# Schemat.net
KiCad netlist of a schematic drawn in Altium Designer
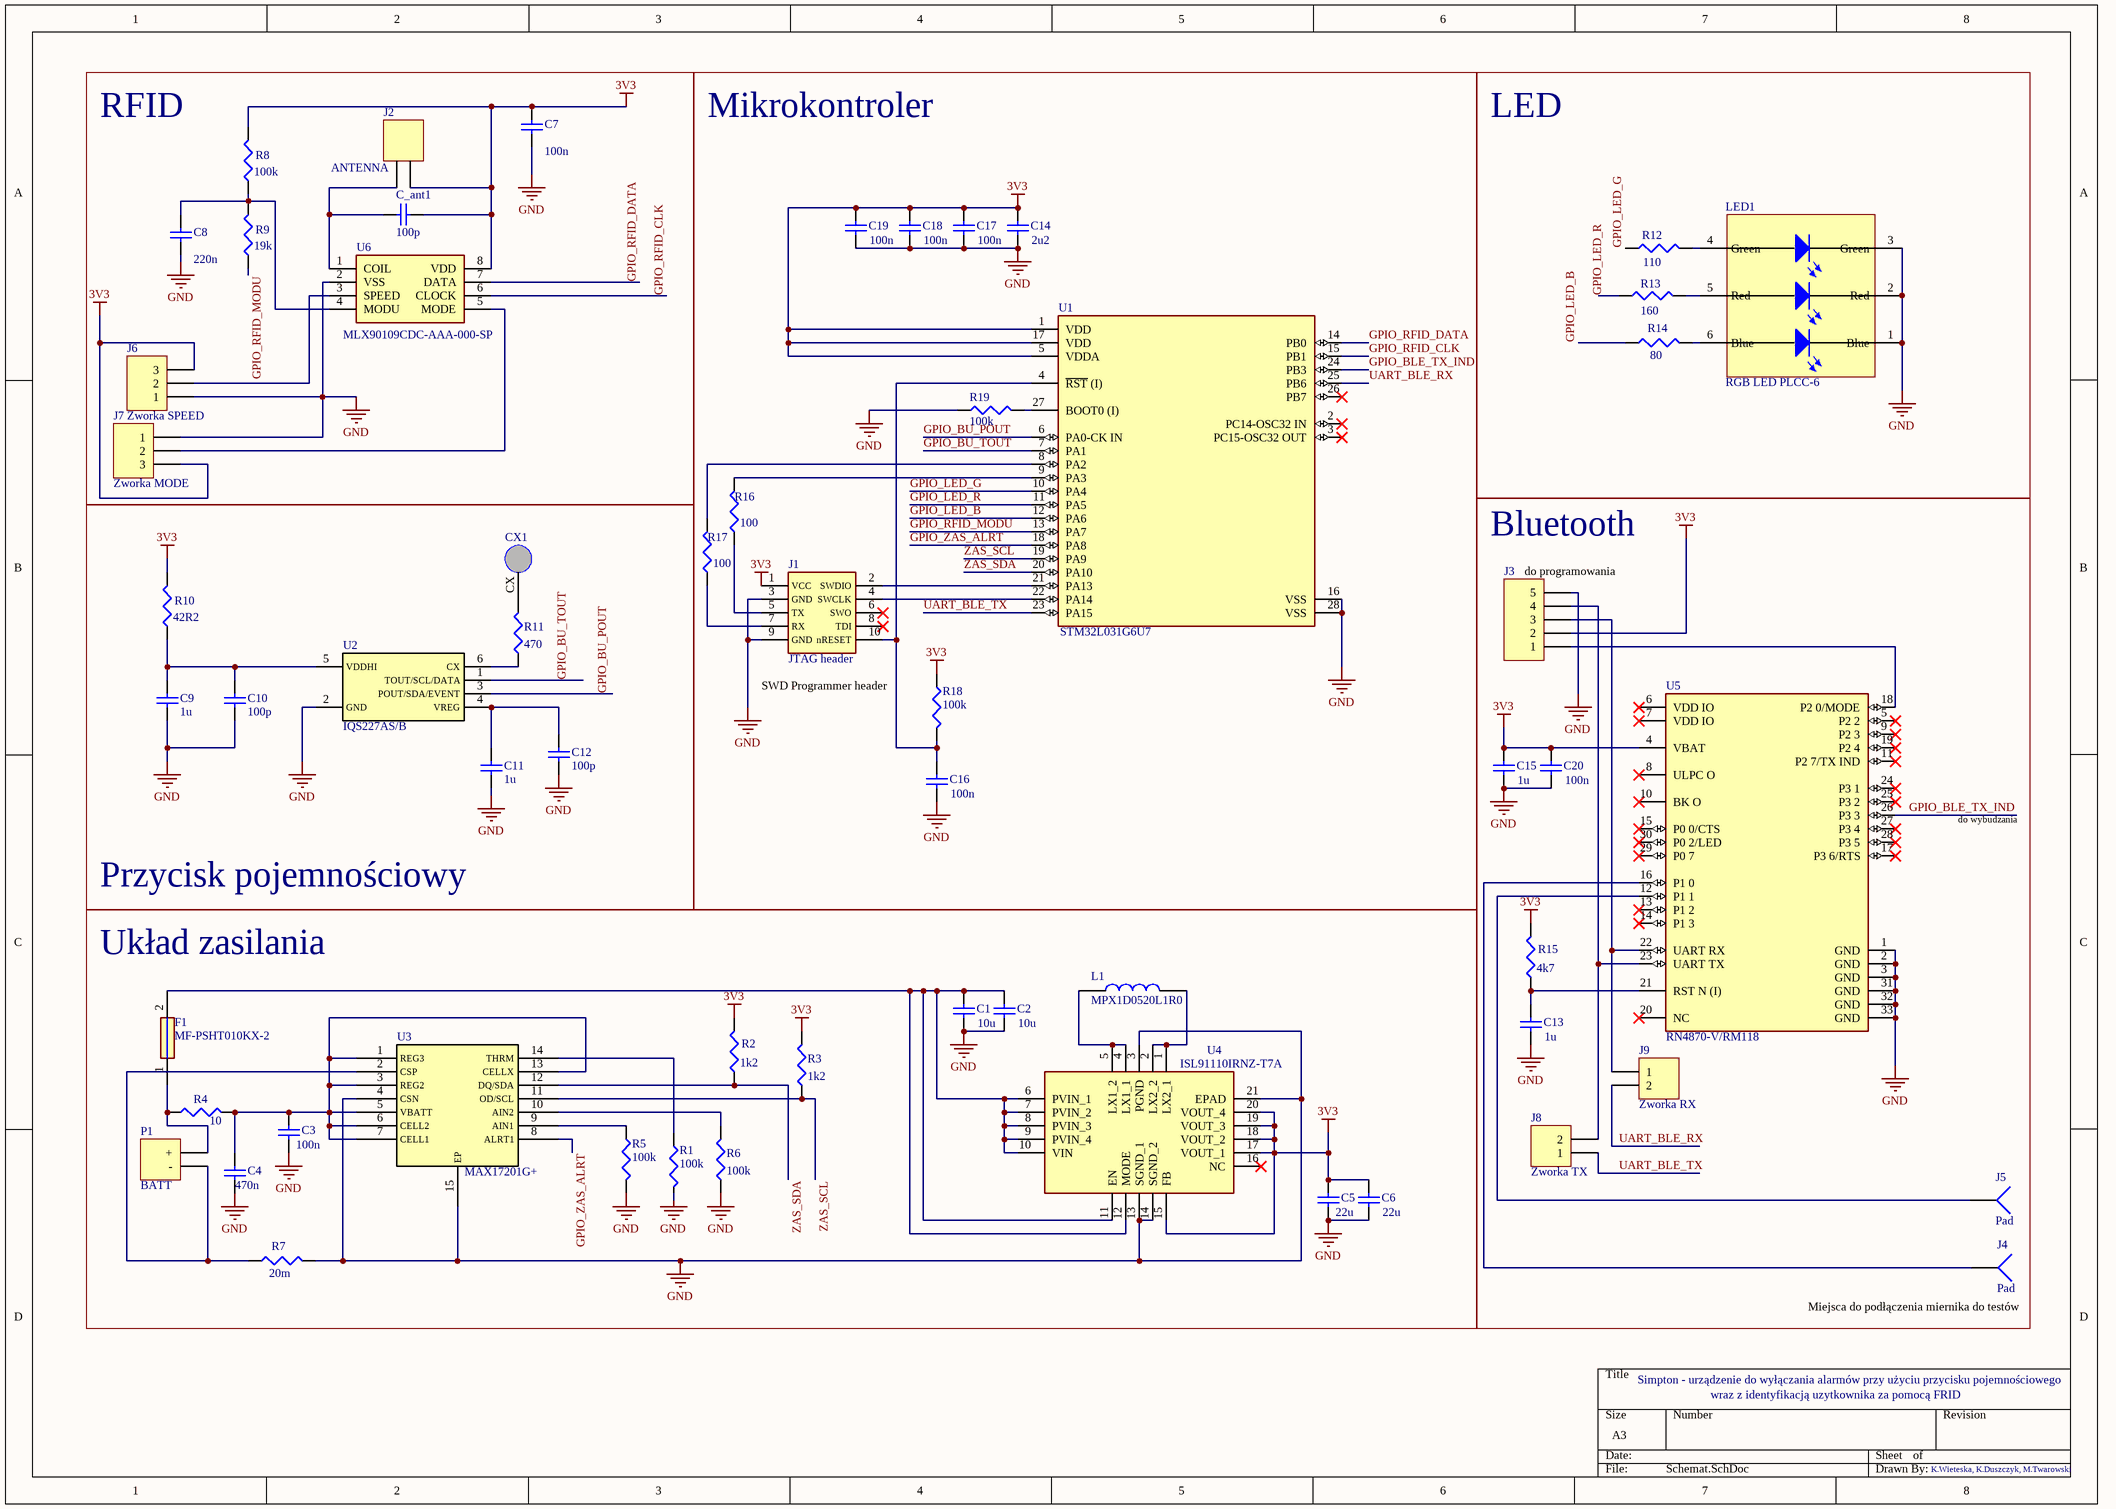
[diagram p0: Schemat.SchDoc]

(export (version "E")
  (design (tool "Eeschema 10.0.6"))
  (components
    (comp (ref "C1")
      (value "10u")
      (footprint "1608[0603]")
      (description "Capacitor (Semiconductor SIM Model)")
      (fields (field (name "Comment") "Cap Semi") (field (name "PUBLISHER") "Altium Limited"))
      (libsource (lib "Miscellaneous Devices") (part "Cap Semi"))
    )
    (comp (ref "C2")
      (value "10u")
      (footprint "1608[0603]")
      (description "Capacitor (Semiconductor SIM Model)")
      (fields (field (name "Comment") "Cap Semi") (field (name "PUBLISHER") "Altium Limited"))
      (libsource (lib "Miscellaneous Devices") (part "Cap Semi"))
    )
    (comp (ref "C3")
      (value "100n")
      (footprint "0402")
      (description "Capacitor (Semiconductor SIM Model)")
      (fields (field (name "Comment") "Cap Semi") (field (name "PUBLISHER") "Altium Limited"))
      (libsource (lib "Miscellaneous Devices") (part "Cap Semi"))
    )
    (comp (ref "C4")
      (value "470n")
      (footprint "0402")
      (description "Capacitor (Semiconductor SIM Model)")
      (fields (field (name "Comment") "Cap Semi") (field (name "PUBLISHER") "Altium Limited"))
      (libsource (lib "Miscellaneous Devices") (part "Cap Semi"))
    )
    (comp (ref "C5")
      (value "22u")
      (footprint "1608[0603]")
      (description "Capacitor (Semiconductor SIM Model)")
      (fields (field (name "Comment") "Cap Semi") (field (name "PUBLISHER") "Altium Limited"))
      (libsource (lib "Miscellaneous Devices") (part "Cap Semi"))
    )
    (comp (ref "C6")
      (value "22u")
      (footprint "1608[0603]")
      (description "Capacitor (Semiconductor SIM Model)")
      (fields (field (name "Comment") "Cap Semi") (field (name "PUBLISHER") "Altium Limited"))
      (libsource (lib "Miscellaneous Devices") (part "Cap Semi"))
    )
    (comp (ref "C7")
      (value "100n")
      (footprint "0402")
      (description "Capacitor (Semiconductor SIM Model)")
      (fields (field (name "Comment") "Cap Semi") (field (name "PUBLISHER") "Altium Limited"))
      (libsource (lib "Miscellaneous Devices") (part "Cap Semi"))
    )
    (comp (ref "C8")
      (value "220n")
      (footprint "0402")
      (description "Capacitor (Semiconductor SIM Model)")
      (fields (field (name "Comment") "Cap Semi") (field (name "PUBLISHER") "Altium Limited"))
      (libsource (lib "Miscellaneous Devices") (part "Cap Semi"))
    )
    (comp (ref "C9")
      (value "1u")
      (footprint "0402")
      (description "Capacitor (Semiconductor SIM Model)")
      (fields (field (name "Comment") "Cap Semi") (field (name "PUBLISHER") "Altium Limited"))
      (libsource (lib "Miscellaneous Devices") (part "Cap Semi"))
    )
    (comp (ref "C10")
      (value "100p")
      (footprint "0402")
      (description "Capacitor (Semiconductor SIM Model)")
      (fields (field (name "Comment") "Cap Semi") (field (name "PUBLISHER") "Altium Limited"))
      (libsource (lib "Miscellaneous Devices") (part "Cap Semi"))
    )
    (comp (ref "C11")
      (value "1u")
      (footprint "0402")
      (description "Capacitor (Semiconductor SIM Model)")
      (fields (field (name "Comment") "Cap Semi") (field (name "PUBLISHER") "Altium Limited"))
      (libsource (lib "Miscellaneous Devices") (part "Cap Semi"))
    )
    (comp (ref "C12")
      (value "100p")
      (footprint "0402")
      (description "Capacitor (Semiconductor SIM Model)")
      (fields (field (name "Comment") "Cap Semi") (field (name "PUBLISHER") "Altium Limited"))
      (libsource (lib "Miscellaneous Devices") (part "Cap Semi"))
    )
    (comp (ref "C13")
      (value "1u")
      (footprint "0402")
      (description "Capacitor (Semiconductor SIM Model)")
      (fields (field (name "Comment") "Cap Semi") (field (name "PUBLISHER") "Altium Limited"))
      (libsource (lib "Miscellaneous Devices") (part "Cap Semi"))
    )
    (comp (ref "C14")
      (value "2u2")
      (footprint "0402")
      (description "Capacitor (Semiconductor SIM Model)")
      (fields (field (name "Comment") "Cap Semi") (field (name "PUBLISHER") "Altium Limited"))
      (libsource (lib "Miscellaneous Devices") (part "Cap Semi"))
    )
    (comp (ref "C15")
      (value "1u")
      (footprint "0402")
      (description "Capacitor (Semiconductor SIM Model)")
      (fields (field (name "Comment") "Cap Semi") (field (name "PUBLISHER") "Altium Limited"))
      (libsource (lib "Miscellaneous Devices") (part "Cap Semi"))
    )
    (comp (ref "C16")
      (value "100n")
      (footprint "0402")
      (description "Capacitor (Semiconductor SIM Model)")
      (fields (field (name "Comment") "Cap Semi") (field (name "PUBLISHER") "Altium Limited"))
      (libsource (lib "Miscellaneous Devices") (part "Cap Semi"))
    )
    (comp (ref "C17")
      (value "100n")
      (footprint "0402")
      (description "Capacitor (Semiconductor SIM Model)")
      (fields (field (name "Comment") "Cap Semi") (field (name "PUBLISHER") "Altium Limited"))
      (libsource (lib "Miscellaneous Devices") (part "Cap Semi"))
    )
    (comp (ref "C18")
      (value "100n")
      (footprint "0402")
      (description "Capacitor (Semiconductor SIM Model)")
      (fields (field (name "Comment") "Cap Semi") (field (name "PUBLISHER") "Altium Limited"))
      (libsource (lib "Miscellaneous Devices") (part "Cap Semi"))
    )
    (comp (ref "C19")
      (value "100n")
      (footprint "0402")
      (description "Capacitor (Semiconductor SIM Model)")
      (fields (field (name "Comment") "Cap Semi") (field (name "PUBLISHER") "Altium Limited"))
      (libsource (lib "Miscellaneous Devices") (part "Cap Semi"))
    )
    (comp (ref "C20")
      (value "100n")
      (footprint "0402")
      (description "Capacitor (Semiconductor SIM Model)")
      (fields (field (name "Comment") "Cap Semi") (field (name "PUBLISHER") "Altium Limited"))
      (libsource (lib "Miscellaneous Devices") (part "Cap Semi"))
    )
    (comp (ref "CX1")
      (value "KD_electrode")
      (footprint "Simpton_PcbLib:KD_electrode")
      (libsource (lib "Simpton_Schlib") (part "KD_electrode"))
    )
    (comp (ref "C_ant1")
      (value "100p")
      (footprint "C1206")
      (description "Capacitor (Semiconductor SIM Model)")
      (fields (field (name "Comment") "Cap Semi") (field (name "PUBLISHER") "Altium Limited"))
      (libsource (lib "Miscellaneous Devices") (part "Cap Semi"))
    )
    (comp (ref "F1")
      (value "MF-PSHT010KX-2")
      (footprint "Simpton_PcbLib:FUSC2214X120N")
      (description "Fuse")
      (fields
        (field (name "MANUFACTURER_PART_NUMBER") "MF-PSHT050KX-2")
        (field (name "MOUSER PART NUMBER") "652-MF-PSHT050KX-2")
      )
      (libsource (lib "Simpton_Schlib") (part "MF-PSHT010KX-2"))
    )
    (comp (ref "J1")
      (value "JTAG header")
      (footprint "Simpton_PcbLib:KD_JTAG_header")
      (description "Connector")
      (libsource (lib "Simpton_Schlib") (part "KD_JTAG_connector"))
    )
    (comp (ref "J2")
      (value "ANTENNA")
      (footprint "HDR1X2")
      (description "Header, 2-Pin")
      (fields (field (name "PUBLISHER") "Altium Limited"))
      (libsource (lib "") (part "Header 2_2"))
    )
    (comp (ref "J3")
      (value "Header 5")
      (footprint "HDR1X5")
      (description "Header, 5-Pin")
      (fields (field (name "PUBLISHER") "Altium Limited"))
      (libsource (lib "Miscellaneous Connectors") (part "Header 5"))
    )
    (comp (ref "J4")
      (value "Pad")
      (footprint "PIN1")
      (fields (field (name "PUBLISHER") "Altium Limited"))
      (libsource (lib "Miscellaneous Connectors") (part "Socket"))
    )
    (comp (ref "J5")
      (value "Pad")
      (footprint "PIN1")
      (fields (field (name "PUBLISHER") "Altium Limited"))
      (libsource (lib "Miscellaneous Connectors") (part "Socket"))
    )
    (comp (ref "J6")
      (value "Zworka SPEED")
      (footprint "HDR1X3")
      (description "Header, 3-Pin")
      (fields (field (name "PUBLISHER") "Altium Limited"))
      (libsource (lib "") (part "Header 3_1"))
    )
    (comp (ref "J7")
      (value "Zworka MODE")
      (footprint "HDR1X3")
      (description "Header, 3-Pin")
      (fields (field (name "PUBLISHER") "Altium Limited"))
      (libsource (lib "Miscellaneous Connectors") (part "Header 3"))
    )
    (comp (ref "J8")
      (value "Zworka TX")
      (footprint "HDR1X2")
      (description "Header, 2-Pin")
      (fields (field (name "PUBLISHER") "Altium Limited"))
      (libsource (lib "Miscellaneous Connectors") (part "Header 2"))
    )
    (comp (ref "J9")
      (value "Zworka RX")
      (footprint "HDR1X2")
      (description "Header, 2-Pin")
      (fields (field (name "PUBLISHER") "Altium Limited"))
      (libsource (lib "") (part "Header 2_3"))
    )
    (comp (ref "L1")
      (value "MPX1D0520L1R0")
      (footprint "Simpton_PcbLib:INDPM5350X200N")
      (libsource (lib "Simpton_Schlib") (part "KD_cewka"))
    )
    (comp (ref "LED1")
      (value "RGB LED PLCC-6")
      (footprint "Simpton_PcbLib:5050")
      (libsource (lib "Simpton_Schlib") (part "KD_PLCC-6"))
    )
    (comp (ref "P1")
      (value "BATT")
      (footprint "HDR1X2")
      (description "Header, 2-Pin")
      (fields (field (name "PUBLISHER") "Altium Limited"))
      (libsource (lib "") (part "Header 2_1"))
    )
    (comp (ref "R1")
      (value "100k")
      (footprint "J1-0603")
      (description "Resistor")
      (fields (field (name "Comment") "Res3") (field (name "PUBLISHER") "Altium Limited"))
      (libsource (lib "Miscellaneous Devices") (part "Res3"))
    )
    (comp (ref "R2")
      (value "1k2")
      (footprint "J1-0603")
      (description "Resistor")
      (fields (field (name "Comment") "Res3") (field (name "PUBLISHER") "Altium Limited"))
      (libsource (lib "Miscellaneous Devices") (part "Res3"))
    )
    (comp (ref "R3")
      (value "1k2")
      (footprint "J1-0603")
      (description "Resistor")
      (fields (field (name "Comment") "Res3") (field (name "PUBLISHER") "Altium Limited"))
      (libsource (lib "Miscellaneous Devices") (part "Res3"))
    )
    (comp (ref "R4")
      (value "10")
      (footprint "J1-0603")
      (description "Resistor")
      (fields (field (name "Comment") "Res3") (field (name "PUBLISHER") "Altium Limited"))
      (libsource (lib "Miscellaneous Devices") (part "Res3"))
    )
    (comp (ref "R5")
      (value "100k")
      (footprint "J1-0603")
      (description "Resistor")
      (fields (field (name "Comment") "Res3") (field (name "PUBLISHER") "Altium Limited"))
      (libsource (lib "Miscellaneous Devices") (part "Res3"))
    )
    (comp (ref "R6")
      (value "100k")
      (footprint "J1-0603")
      (description "Resistor")
      (fields (field (name "Comment") "Res3") (field (name "PUBLISHER") "Altium Limited"))
      (libsource (lib "Miscellaneous Devices") (part "Res3"))
    )
    (comp (ref "R7")
      (value "20m")
      (footprint "J1-0603")
      (description "Resistor")
      (fields (field (name "Comment") "Res3") (field (name "PUBLISHER") "Altium Limited"))
      (libsource (lib "Miscellaneous Devices") (part "Res3"))
    )
    (comp (ref "R8")
      (value "100k")
      (footprint "J1-0603")
      (description "Resistor")
      (fields (field (name "Comment") "Res3") (field (name "PUBLISHER") "Altium Limited"))
      (libsource (lib "Miscellaneous Devices") (part "Res3"))
    )
    (comp (ref "R9")
      (value "19k")
      (footprint "J1-0603")
      (description "Resistor")
      (fields (field (name "Comment") "Res3") (field (name "PUBLISHER") "Altium Limited"))
      (libsource (lib "Miscellaneous Devices") (part "Res3"))
    )
    (comp (ref "R10")
      (value "42R2")
      (footprint "J1-0603")
      (description "Resistor")
      (fields (field (name "Comment") "Res3") (field (name "PUBLISHER") "Altium Limited"))
      (libsource (lib "Miscellaneous Devices") (part "Res3"))
    )
    (comp (ref "R11")
      (value "470")
      (footprint "J1-0603")
      (description "Resistor")
      (fields (field (name "Comment") "Res3") (field (name "PUBLISHER") "Altium Limited"))
      (libsource (lib "Miscellaneous Devices") (part "Res3"))
    )
    (comp (ref "R12")
      (value "110")
      (footprint "J1-0603")
      (description "Resistor")
      (fields (field (name "Comment") "Res3") (field (name "PUBLISHER") "Altium Limited"))
      (libsource (lib "Miscellaneous Devices") (part "Res3"))
    )
    (comp (ref "R13")
      (value "160")
      (footprint "J1-0603")
      (description "Resistor")
      (fields (field (name "Comment") "Res3") (field (name "PUBLISHER") "Altium Limited"))
      (libsource (lib "Miscellaneous Devices") (part "Res3"))
    )
    (comp (ref "R14")
      (value "80")
      (footprint "J1-0603")
      (description "Resistor")
      (fields (field (name "Comment") "Res3") (field (name "PUBLISHER") "Altium Limited"))
      (libsource (lib "Miscellaneous Devices") (part "Res3"))
    )
    (comp (ref "R15")
      (value "4k7")
      (footprint "J1-0603")
      (description "Resistor")
      (fields (field (name "Comment") "Res3") (field (name "PUBLISHER") "Altium Limited"))
      (libsource (lib "Miscellaneous Devices") (part "Res3"))
    )
    (comp (ref "R16")
      (value "100")
      (footprint "J1-0603")
      (description "Resistor")
      (fields (field (name "Comment") "Res3") (field (name "PUBLISHER") "Altium Limited"))
      (libsource (lib "Miscellaneous Devices") (part "Res3"))
    )
    (comp (ref "R17")
      (value "100")
      (footprint "J1-0603")
      (description "Resistor")
      (fields (field (name "Comment") "Res3") (field (name "PUBLISHER") "Altium Limited"))
      (libsource (lib "Miscellaneous Devices") (part "Res3"))
    )
    (comp (ref "R18")
      (value "100k")
      (footprint "J1-0603")
      (description "Resistor")
      (fields (field (name "Comment") "Res3") (field (name "PUBLISHER") "Altium Limited"))
      (libsource (lib "Miscellaneous Devices") (part "Res3"))
    )
    (comp (ref "R19")
      (value "100k")
      (footprint "J1-0603")
      (description "Resistor")
      (fields (field (name "Comment") "Res3") (field (name "PUBLISHER") "Altium Limited"))
      (libsource (lib "Miscellaneous Devices") (part "Res3"))
    )
    (comp (ref "U1")
      (value "STM32L031G6U7")
      (footprint "FP-UFQFPN28-A0B0-MFG")
      (description "IC MCU 32BIT 32KB FLASH 28UFQFPN")
      (libsource (lib "Altium Content Vault") (part "cf8d419c7f1ef5ba6492875b64af71c"))
    )
    (comp (ref "U2")
      (value "IQS227AS/B")
      (footprint "Simpton_PcbLib:KD_TSOT23-6")
      (libsource (lib "Simpton_Schlib") (part "KD_IQS227AS/B"))
    )
    (comp (ref "U3")
      (value "MAX17201G+")
      (footprint "Simpton_PcbLib:KW_TDFN14")
      (libsource (lib "Simpton_Schlib") (part "MAX17201G+"))
    )
    (comp (ref "U4")
      (value "ISL91110IRNZ-T7A")
      (footprint "Simpton_PcbLib:QFN50P400X400X100-21N")
      (description "LED")
      (fields (field (name "MOUSER PART NUMBER") "968-ISL91110IRNZ-T7A"))
      (libsource (lib "*") (part "ISL91110IRNZ-T7A"))
    )
    (comp (ref "U5")
      (value "RN4870-V/RM118")
      (footprint "FP-RN4870-V-RM118-MFG")
      (description "RX TXRX MOD BLE 5.0 CHIP SMD")
      (libsource (lib "Altium Content Vault") (part "71faa6225239f173ba86639d1c0a630"))
    )
    (comp (ref "U6")
      (value "MLX90109CDC-AAA-000-SP")
      (footprint "Simpton_PcbLib:SOIC127P600X172-8N")
      (description "Hardware")
      (fields (field (name "MOUSER PART NUMBER") "482-90109CDCAAA000SP"))
      (libsource (lib "*") (part "MLX90109CDC-AAA-000-SP"))
    )
  )
  (nets
    (net (code "1") (name "/GPIO_BLE_TX_IND") (class "Default")
      (node (ref "U1") (pin "24") (pinfunction "PB3_24") (pintype "bidirectional"))
      (node (ref "U5") (pin "26") (pinfunction "P3_3_26") (pintype "bidirectional"))
    )
    (net (code "2") (name "/GPIO_BU_POUT") (class "Default")
      (node (ref "U1") (pin "6") (pinfunction "PA0-CK_IN_6") (pintype "bidirectional"))
      (node (ref "U2") (pin "3") (pinfunction "POUT/SDA/EVENT_3") (pintype "passive"))
    )
    (net (code "3") (name "/GPIO_BU_TOUT") (class "Default")
      (node (ref "U1") (pin "7") (pinfunction "PA1_7") (pintype "bidirectional"))
      (node (ref "U2") (pin "1") (pinfunction "TOUT/SCL/DATA_1") (pintype "passive"))
    )
    (net (code "4") (name "/GPIO_LED_B") (class "Default")
      (node (ref "R14") (pin "1") (pinfunction "1_1") (pintype "passive"))
      (node (ref "U1") (pin "12") (pinfunction "PA6_12") (pintype "bidirectional"))
    )
    (net (code "5") (name "/GPIO_LED_G") (class "Default")
      (node (ref "R12") (pin "1") (pinfunction "1_1") (pintype "passive"))
      (node (ref "U1") (pin "10") (pinfunction "PA4_10") (pintype "bidirectional"))
    )
    (net (code "6") (name "/GPIO_LED_R") (class "Default")
      (node (ref "R13") (pin "1") (pinfunction "1_1") (pintype "passive"))
      (node (ref "U1") (pin "11") (pinfunction "PA5_11") (pintype "bidirectional"))
    )
    (net (code "7") (name "/GPIO_RFID_CLK") (class "Default")
      (node (ref "U1") (pin "15") (pinfunction "PB1_15") (pintype "bidirectional"))
      (node (ref "U6") (pin "6") (pinfunction "CLOCK_6") (pintype "passive"))
    )
    (net (code "8") (name "/GPIO_RFID_DATA") (class "Default")
      (node (ref "U1") (pin "14") (pinfunction "PB0_14") (pintype "bidirectional"))
      (node (ref "U6") (pin "7") (pinfunction "DATA_7") (pintype "passive"))
    )
    (net (code "9") (name "/GPIO_RFID_MODU") (class "Default")
      (node (ref "R9") (pin "1") (pinfunction "1_1") (pintype "passive"))
      (node (ref "U1") (pin "13") (pinfunction "PA7_13") (pintype "bidirectional"))
    )
    (net (code "10") (name "/GPIO_ZAS_ALRT") (class "Default")
      (node (ref "U1") (pin "18") (pinfunction "PA8_18") (pintype "bidirectional"))
      (node (ref "U3") (pin "8") (pinfunction "ALRT1_8") (pintype "passive"))
    )
    (net (code "11") (name "/UART_BLE_RX") (class "Default")
      (node (ref "J9") (pin "2") (pinfunction "2_2") (pintype "passive"))
      (node (ref "U1") (pin "25") (pinfunction "PB6_25") (pintype "bidirectional"))
    )
    (net (code "12") (name "/UART_BLE_TX") (class "Default")
      (node (ref "J8") (pin "1") (pinfunction "1_1") (pintype "passive"))
      (node (ref "U1") (pin "23") (pinfunction "PA15_23") (pintype "bidirectional"))
    )
    (net (code "13") (name "/ZAS_SCL") (class "Default")
      (node (ref "R3") (pin "1") (pinfunction "1_1") (pintype "passive"))
      (node (ref "U1") (pin "19") (pinfunction "PA9_19") (pintype "bidirectional"))
      (node (ref "U3") (pin "11") (pinfunction "OD/SCL_11") (pintype "passive"))
    )
    (net (code "14") (name "/ZAS_SDA") (class "Default")
      (node (ref "R2") (pin "1") (pinfunction "1_1") (pintype "passive"))
      (node (ref "U1") (pin "20") (pinfunction "PA10_20") (pintype "bidirectional"))
      (node (ref "U3") (pin "12") (pinfunction "DQ/SDA_12") (pintype "passive"))
    )
    (net (code "15") (name "3V3") (class "Default")
      (node (ref "C14") (pin "1") (pinfunction "1_1") (pintype "passive"))
      (node (ref "C15") (pin "1") (pinfunction "1_1") (pintype "passive"))
      (node (ref "C17") (pin "1") (pinfunction "1_1") (pintype "passive"))
      (node (ref "C18") (pin "1") (pinfunction "1_1") (pintype "passive"))
      (node (ref "C19") (pin "1") (pinfunction "1_1") (pintype "passive"))
      (node (ref "C20") (pin "1") (pinfunction "1_1") (pintype "passive"))
      (node (ref "C5") (pin "1") (pinfunction "1_1") (pintype "passive"))
      (node (ref "C6") (pin "1") (pinfunction "1_1") (pintype "passive"))
      (node (ref "C7") (pin "2") (pinfunction "2_2") (pintype "passive"))
      (node (ref "C_ant1") (pin "1") (pinfunction "1_1") (pintype "passive"))
      (node (ref "J1") (pin "1") (pinfunction "VCC_1") (pintype "passive"))
      (node (ref "J2") (pin "2") (pinfunction "+_2") (pintype "passive"))
      (node (ref "J3") (pin "2") (pinfunction "2_2") (pintype "passive"))
      (node (ref "J6") (pin "3") (pinfunction "3_3") (pintype "passive"))
      (node (ref "J7") (pin "3") (pinfunction "3_3") (pintype "passive"))
      (node (ref "R10") (pin "2") (pinfunction "2_2") (pintype "passive"))
      (node (ref "R15") (pin "2") (pinfunction "2_2") (pintype "passive"))
      (node (ref "R18") (pin "1") (pinfunction "1_1") (pintype "passive"))
      (node (ref "R2") (pin "2") (pinfunction "2_2") (pintype "passive"))
      (node (ref "R3") (pin "2") (pinfunction "2_2") (pintype "passive"))
      (node (ref "R8") (pin "2") (pinfunction "2_2") (pintype "passive"))
      (node (ref "U1") (pin "1") (pinfunction "VDD_1") (pintype "power_in"))
      (node (ref "U1") (pin "17") (pinfunction "VDD_17") (pintype "power_in"))
      (node (ref "U1") (pin "5") (pinfunction "VDDA_5") (pintype "power_in"))
      (node (ref "U4") (pin "15") (pinfunction "FB_15") (pintype "passive"))
      (node (ref "U4") (pin "17") (pinfunction "VOUT_1_17") (pintype "passive"))
      (node (ref "U4") (pin "18") (pinfunction "VOUT_2_18") (pintype "passive"))
      (node (ref "U4") (pin "19") (pinfunction "VOUT_3_19") (pintype "passive"))
      (node (ref "U4") (pin "20") (pinfunction "VOUT_4_20") (pintype "passive"))
      (node (ref "U5") (pin "4") (pinfunction "VBAT_4") (pintype "power_in"))
      (node (ref "U6") (pin "8") (pinfunction "VDD_8") (pintype "passive"))
    )
    (net (code "16") (name "GND") (class "Default")
      (node (ref "C1") (pin "2") (pinfunction "2_2") (pintype "passive"))
      (node (ref "C10") (pin "2") (pinfunction "2_2") (pintype "passive"))
      (node (ref "C11") (pin "2") (pinfunction "2_2") (pintype "passive"))
      (node (ref "C12") (pin "2") (pinfunction "2_2") (pintype "passive"))
      (node (ref "C13") (pin "2") (pinfunction "2_2") (pintype "passive"))
      (node (ref "C14") (pin "2") (pinfunction "2_2") (pintype "passive"))
      (node (ref "C15") (pin "2") (pinfunction "2_2") (pintype "passive"))
      (node (ref "C16") (pin "2") (pinfunction "2_2") (pintype "passive"))
      (node (ref "C17") (pin "2") (pinfunction "2_2") (pintype "passive"))
      (node (ref "C18") (pin "2") (pinfunction "2_2") (pintype "passive"))
      (node (ref "C19") (pin "2") (pinfunction "2_2") (pintype "passive"))
      (node (ref "C2") (pin "2") (pinfunction "2_2") (pintype "passive"))
      (node (ref "C20") (pin "2") (pinfunction "2_2") (pintype "passive"))
      (node (ref "C3") (pin "2") (pinfunction "2_2") (pintype "passive"))
      (node (ref "C4") (pin "2") (pinfunction "2_2") (pintype "passive"))
      (node (ref "C5") (pin "2") (pinfunction "2_2") (pintype "passive"))
      (node (ref "C6") (pin "2") (pinfunction "2_2") (pintype "passive"))
      (node (ref "C7") (pin "1") (pinfunction "1_1") (pintype "passive"))
      (node (ref "C8") (pin "1") (pinfunction "1_1") (pintype "passive"))
      (node (ref "C9") (pin "2") (pinfunction "2_2") (pintype "passive"))
      (node (ref "J1") (pin "3") (pinfunction "GND_3") (pintype "passive"))
      (node (ref "J1") (pin "9") (pinfunction "GND_9") (pintype "passive"))
      (node (ref "J3") (pin "5") (pinfunction "5_5") (pintype "passive"))
      (node (ref "J6") (pin "1") (pinfunction "1_1") (pintype "passive"))
      (node (ref "J7") (pin "1") (pinfunction "1_1") (pintype "passive"))
      (node (ref "LED1") (pin "1") (pinfunction "Blue_1") (pintype "passive"))
      (node (ref "LED1") (pin "2") (pinfunction "Red_2") (pintype "passive"))
      (node (ref "LED1") (pin "3") (pinfunction "Green_3") (pintype "passive"))
      (node (ref "R1") (pin "2") (pinfunction "2_2") (pintype "passive"))
      (node (ref "R19") (pin "1") (pinfunction "1_1") (pintype "passive"))
      (node (ref "R5") (pin "2") (pinfunction "2_2") (pintype "passive"))
      (node (ref "R6") (pin "1") (pinfunction "1_1") (pintype "passive"))
      (node (ref "R7") (pin "2") (pinfunction "2_2") (pintype "passive"))
      (node (ref "U1") (pin "16") (pinfunction "VSS_16") (pintype "power_in"))
      (node (ref "U1") (pin "28") (pinfunction "VSS_28") (pintype "power_in"))
      (node (ref "U2") (pin "2") (pinfunction "GND_2") (pintype "passive"))
      (node (ref "U3") (pin "15") (pinfunction "EP_15") (pintype "passive"))
      (node (ref "U3") (pin "4") (pinfunction "CSN_4") (pintype "passive"))
      (node (ref "U4") (pin "13") (pinfunction "SGND_1_13") (pintype "passive"))
      (node (ref "U4") (pin "14") (pinfunction "SGND_2_14") (pintype "passive"))
      (node (ref "U4") (pin "21") (pinfunction "EPAD_21") (pintype "passive"))
      (node (ref "U4") (pin "3") (pinfunction "PGND_3") (pintype "passive"))
      (node (ref "U5") (pin "1") (pinfunction "GND_1") (pintype "power_in"))
      (node (ref "U5") (pin "2") (pinfunction "GND_2") (pintype "power_in"))
      (node (ref "U5") (pin "3") (pinfunction "GND_3") (pintype "power_in"))
      (node (ref "U5") (pin "31") (pinfunction "GND_31") (pintype "power_in"))
      (node (ref "U5") (pin "32") (pinfunction "GND_32") (pintype "power_in"))
      (node (ref "U5") (pin "33") (pinfunction "GND_33") (pintype "power_in"))
      (node (ref "U6") (pin "2") (pinfunction "VSS_2") (pintype "passive"))
    )
    (net (code "17") (name "Net-(CX1-18)") (class "Default")
      (node (ref "CX1") (pin "CX") (pinfunction "18_CX") (pintype "passive"))
      (node (ref "R11") (pin "2") (pinfunction "2_2") (pintype "passive"))
    )
    (net (code "18") (name "Net-(J1-RX)") (class "Default")
      (node (ref "J1") (pin "7") (pinfunction "RX_7") (pintype "passive"))
      (node (ref "R17") (pin "1") (pinfunction "1_1") (pintype "passive"))
    )
    (net (code "19") (name "Net-(J1-SWCLK)") (class "Default")
      (node (ref "J1") (pin "4") (pinfunction "SWCLK_4") (pintype "passive"))
      (node (ref "U1") (pin "22") (pinfunction "PA14_22") (pintype "bidirectional"))
    )
    (net (code "20") (name "Net-(J1-SWDIO)") (class "Default")
      (node (ref "J1") (pin "2") (pinfunction "SWDIO_2") (pintype "passive"))
      (node (ref "U1") (pin "21") (pinfunction "PA13_21") (pintype "bidirectional"))
    )
    (net (code "21") (name "Net-(J1-TX)") (class "Default")
      (node (ref "J1") (pin "5") (pinfunction "TX_5") (pintype "passive"))
      (node (ref "R16") (pin "1") (pinfunction "1_1") (pintype "passive"))
    )
    (net (code "22") (name "Net-(J1-nRESET)") (class "Default")
      (node (ref "C16") (pin "1") (pinfunction "1_1") (pintype "passive"))
      (node (ref "J1") (pin "10") (pinfunction "nRESET_10") (pintype "passive"))
      (node (ref "R18") (pin "2") (pinfunction "2_2") (pintype "passive"))
      (node (ref "U1") (pin "4") (pinfunction "~{RST}_(I)_4") (pintype "passive"))
    )
    (net (code "23") (name "Net-(J2--)") (class "Default")
      (node (ref "C_ant1") (pin "2") (pinfunction "2_2") (pintype "passive"))
      (node (ref "J2") (pin "1") (pinfunction "-_1") (pintype "passive"))
      (node (ref "U6") (pin "1") (pinfunction "COIL_1") (pintype "passive"))
    )
    (net (code "24") (name "Net-(LED1-Blue-Pad6)") (class "Default")
      (node (ref "LED1") (pin "6") (pinfunction "Blue_6") (pintype "passive"))
      (node (ref "R14") (pin "2") (pinfunction "2_2") (pintype "passive"))
    )
    (net (code "25") (name "Net-(LED1-Green-Pad4)") (class "Default")
      (node (ref "LED1") (pin "4") (pinfunction "Green_4") (pintype "passive"))
      (node (ref "R12") (pin "2") (pinfunction "2_2") (pintype "passive"))
    )
    (net (code "26") (name "Net-(LED1-Red-Pad5)") (class "Default")
      (node (ref "LED1") (pin "5") (pinfunction "Red_5") (pintype "passive"))
      (node (ref "R13") (pin "2") (pinfunction "2_2") (pintype "passive"))
    )
    (net (code "27") (name "Net-(P1-+)") (class "Default")
      (node (ref "F1") (pin "1") (pinfunction "1_1") (pintype "passive"))
      (node (ref "P1") (pin "2") (pinfunction "+_2") (pintype "passive"))
      (node (ref "R4") (pin "1") (pinfunction "1_1") (pintype "passive"))
    )
    (net (code "28") (name "Net-(P1--)") (class "Default")
      (node (ref "P1") (pin "1") (pinfunction "-_1") (pintype "passive"))
      (node (ref "R7") (pin "1") (pinfunction "1_1") (pintype "passive"))
      (node (ref "U3") (pin "2") (pinfunction "CSP_2") (pintype "passive"))
    )
    (net (code "29") (name "Net-(U1-BOOT0_(I))") (class "Default")
      (node (ref "R19") (pin "2") (pinfunction "2_2") (pintype "passive"))
      (node (ref "U1") (pin "27") (pinfunction "BOOT0_(I)_27") (pintype "passive"))
    )
    (net (code "30") (name "Net-(U1-PA2)") (class "Default")
      (node (ref "R17") (pin "2") (pinfunction "2_2") (pintype "passive"))
      (node (ref "U1") (pin "8") (pinfunction "PA2_8") (pintype "bidirectional"))
    )
    (net (code "31") (name "Net-(U1-PA3)") (class "Default")
      (node (ref "R16") (pin "2") (pinfunction "2_2") (pintype "passive"))
      (node (ref "U1") (pin "9") (pinfunction "PA3_9") (pintype "bidirectional"))
    )
    (net (code "32") (name "Net-(U2-CX)") (class "Default")
      (node (ref "R11") (pin "1") (pinfunction "1_1") (pintype "passive"))
      (node (ref "U2") (pin "6") (pinfunction "CX_6") (pintype "passive"))
    )
    (net (code "33") (name "Net-(U2-VDDHI)") (class "Default")
      (node (ref "C10") (pin "1") (pinfunction "1_1") (pintype "passive"))
      (node (ref "C9") (pin "1") (pinfunction "1_1") (pintype "passive"))
      (node (ref "R10") (pin "1") (pinfunction "1_1") (pintype "passive"))
      (node (ref "U2") (pin "5") (pinfunction "VDDHI_5") (pintype "passive"))
    )
    (net (code "34") (name "Net-(U2-VREG)") (class "Default")
      (node (ref "C11") (pin "1") (pinfunction "1_1") (pintype "passive"))
      (node (ref "C12") (pin "1") (pinfunction "1_1") (pintype "passive"))
      (node (ref "U2") (pin "4") (pinfunction "VREG_4") (pintype "passive"))
    )
    (net (code "35") (name "Net-(U3-AIN1)") (class "Default")
      (node (ref "R5") (pin "1") (pinfunction "1_1") (pintype "passive"))
      (node (ref "U3") (pin "9") (pinfunction "AIN1_9") (pintype "passive"))
    )
    (net (code "36") (name "Net-(U3-AIN2)") (class "Default")
      (node (ref "R6") (pin "2") (pinfunction "2_2") (pintype "passive"))
      (node (ref "U3") (pin "10") (pinfunction "AIN2_10") (pintype "passive"))
    )
    (net (code "37") (name "Net-(U3-CELL1)") (class "Default")
      (node (ref "C3") (pin "1") (pinfunction "1_1") (pintype "passive"))
      (node (ref "C4") (pin "1") (pinfunction "1_1") (pintype "passive"))
      (node (ref "R4") (pin "2") (pinfunction "2_2") (pintype "passive"))
      (node (ref "U3") (pin "1") (pinfunction "REG3_1") (pintype "passive"))
      (node (ref "U3") (pin "13") (pinfunction "CELLX_13") (pintype "passive"))
      (node (ref "U3") (pin "3") (pinfunction "REG2_3") (pintype "passive"))
      (node (ref "U3") (pin "5") (pinfunction "VBATT_5") (pintype "passive"))
      (node (ref "U3") (pin "6") (pinfunction "CELL2_6") (pintype "passive"))
      (node (ref "U3") (pin "7") (pinfunction "CELL1_7") (pintype "passive"))
    )
    (net (code "38") (name "Net-(U3-THRM)") (class "Default")
      (node (ref "R1") (pin "1") (pinfunction "1_1") (pintype "passive"))
      (node (ref "U3") (pin "14") (pinfunction "THRM_14") (pintype "passive"))
    )
    (net (code "39") (name "Net-(U4-EN)") (class "Default")
      (node (ref "C1") (pin "1") (pinfunction "1_1") (pintype "passive"))
      (node (ref "C2") (pin "1") (pinfunction "1_1") (pintype "passive"))
      (node (ref "F1") (pin "2") (pinfunction "2_2") (pintype "passive"))
      (node (ref "U4") (pin "10") (pinfunction "VIN_10") (pintype "passive"))
      (node (ref "U4") (pin "11") (pinfunction "EN_11") (pintype "passive"))
      (node (ref "U4") (pin "12") (pinfunction "MODE_12") (pintype "passive"))
      (node (ref "U4") (pin "6") (pinfunction "PVIN_1_6") (pintype "passive"))
      (node (ref "U4") (pin "7") (pinfunction "PVIN_2_7") (pintype "passive"))
      (node (ref "U4") (pin "8") (pinfunction "PVIN_3_8") (pintype "passive"))
      (node (ref "U4") (pin "9") (pinfunction "PVIN_4_9") (pintype "passive"))
    )
    (net (code "40") (name "Net-(U4-LX1_1)") (class "Default")
      (node (ref "L1") (pin "2") (pinfunction "2_2") (pintype "passive"))
      (node (ref "U4") (pin "4") (pinfunction "LX1_1_4") (pintype "passive"))
      (node (ref "U4") (pin "5") (pinfunction "LX1_2_5") (pintype "passive"))
    )
    (net (code "41") (name "Net-(U4-LX2_1)") (class "Default")
      (node (ref "L1") (pin "1") (pinfunction "1_1") (pintype "passive"))
      (node (ref "U4") (pin "1") (pinfunction "LX2_1_1") (pintype "passive"))
      (node (ref "U4") (pin "2") (pinfunction "LX2_2_2") (pintype "passive"))
    )
    (net (code "42") (name "Net-(U5-P1_0)") (class "Default")
      (node (ref "J4") (pin "1") (pinfunction "1_1") (pintype "passive"))
      (node (ref "U5") (pin "16") (pinfunction "P1_0_16") (pintype "bidirectional"))
    )
    (net (code "43") (name "Net-(U5-P1_1)") (class "Default")
      (node (ref "J5") (pin "1") (pinfunction "1_1") (pintype "passive"))
      (node (ref "U5") (pin "12") (pinfunction "P1_1_12") (pintype "bidirectional"))
    )
    (net (code "44") (name "Net-(U5-P2_0{slash}MODE)") (class "Default")
      (node (ref "J3") (pin "1") (pinfunction "1_1") (pintype "passive"))
      (node (ref "U5") (pin "18") (pinfunction "P2_0/MODE_18") (pintype "bidirectional"))
    )
    (net (code "45") (name "Net-(U5-RST_N_(I))") (class "Default")
      (node (ref "C13") (pin "1") (pinfunction "1_1") (pintype "passive"))
      (node (ref "R15") (pin "1") (pinfunction "1_1") (pintype "passive"))
      (node (ref "U5") (pin "21") (pinfunction "RST_N_(I)_21") (pintype "passive"))
    )
    (net (code "46") (name "Net-(U5-UART_RX)") (class "Default")
      (node (ref "J3") (pin "3") (pinfunction "3_3") (pintype "passive"))
      (node (ref "J9") (pin "1") (pinfunction "1_1") (pintype "passive"))
      (node (ref "U5") (pin "22") (pinfunction "UART_RX_22") (pintype "bidirectional"))
    )
    (net (code "47") (name "Net-(U5-UART_TX)") (class "Default")
      (node (ref "J3") (pin "4") (pinfunction "4_4") (pintype "passive"))
      (node (ref "J8") (pin "2") (pinfunction "2_2") (pintype "passive"))
      (node (ref "U5") (pin "23") (pinfunction "UART_TX_23") (pintype "bidirectional"))
    )
    (net (code "48") (name "Net-(U6-MODE)") (class "Default")
      (node (ref "J7") (pin "2") (pinfunction "2_2") (pintype "passive"))
      (node (ref "U6") (pin "5") (pinfunction "MODE_5") (pintype "passive"))
    )
    (net (code "49") (name "Net-(U6-MODU)") (class "Default")
      (node (ref "C8") (pin "2") (pinfunction "2_2") (pintype "passive"))
      (node (ref "R8") (pin "1") (pinfunction "1_1") (pintype "passive"))
      (node (ref "R9") (pin "2") (pinfunction "2_2") (pintype "passive"))
      (node (ref "U6") (pin "4") (pinfunction "MODU_4") (pintype "passive"))
    )
    (net (code "50") (name "Net-(U6-SPEED)") (class "Default")
      (node (ref "J6") (pin "2") (pinfunction "2_2") (pintype "passive"))
      (node (ref "U6") (pin "3") (pinfunction "SPEED_3") (pintype "passive"))
    )
    (net (code "51") (name "unconnected-(J1-SWO-Pad6)") (class "Default")
      (node (ref "J1") (pin "6") (pinfunction "SWO_6") (pintype "passive+no_connect"))
    )
    (net (code "52") (name "unconnected-(J1-TDI-Pad8)") (class "Default")
      (node (ref "J1") (pin "8") (pinfunction "TDI_8") (pintype "passive+no_connect"))
    )
    (net (code "53") (name "unconnected-(U1-PB7-Pad26)") (class "Default")
      (node (ref "U1") (pin "26") (pinfunction "PB7_26") (pintype "bidirectional+no_connect"))
    )
    (net (code "54") (name "unconnected-(U1-PC14-OSC32_IN-Pad2)") (class "Default")
      (node (ref "U1") (pin "2") (pinfunction "PC14-OSC32_IN_2") (pintype "bidirectional+no_connect"))
    )
    (net (code "55") (name "unconnected-(U1-PC15-OSC32_OUT-Pad3)") (class "Default")
      (node (ref "U1") (pin "3") (pinfunction "PC15-OSC32_OUT_3") (pintype "bidirectional+no_connect"))
    )
    (net (code "56") (name "unconnected-(U4-NC-Pad16)") (class "Default")
      (node (ref "U4") (pin "16") (pinfunction "NC_16") (pintype "passive+no_connect"))
    )
    (net (code "57") (name "unconnected-(U5-BK_O-Pad10)") (class "Default")
      (node (ref "U5") (pin "10") (pinfunction "BK_O_10") (pintype "power_in+no_connect"))
    )
    (net (code "58") (name "unconnected-(U5-NC-Pad20)") (class "Default")
      (node (ref "U5") (pin "20") (pinfunction "NC_20") (pintype "passive+no_connect"))
    )
    (net (code "59") (name "unconnected-(U5-P0_0{slash}CTS-Pad15)") (class "Default")
      (node (ref "U5") (pin "15") (pinfunction "P0_0/CTS_15") (pintype "bidirectional+no_connect"))
    )
    (net (code "60") (name "unconnected-(U5-P0_2{slash}LED-Pad30)") (class "Default")
      (node (ref "U5") (pin "30") (pinfunction "P0_2/LED_30") (pintype "bidirectional+no_connect"))
    )
    (net (code "61") (name "unconnected-(U5-P0_7-Pad29)") (class "Default")
      (node (ref "U5") (pin "29") (pinfunction "P0_7_29") (pintype "bidirectional+no_connect"))
    )
    (net (code "62") (name "unconnected-(U5-P1_2-Pad13)") (class "Default")
      (node (ref "U5") (pin "13") (pinfunction "P1_2_13") (pintype "bidirectional+no_connect"))
    )
    (net (code "63") (name "unconnected-(U5-P1_3-Pad14)") (class "Default")
      (node (ref "U5") (pin "14") (pinfunction "P1_3_14") (pintype "bidirectional+no_connect"))
    )
    (net (code "64") (name "unconnected-(U5-P2_2-Pad5)") (class "Default")
      (node (ref "U5") (pin "5") (pinfunction "P2_2_5") (pintype "bidirectional+no_connect"))
    )
    (net (code "65") (name "unconnected-(U5-P2_3-Pad9)") (class "Default")
      (node (ref "U5") (pin "9") (pinfunction "P2_3_9") (pintype "bidirectional+no_connect"))
    )
    (net (code "66") (name "unconnected-(U5-P2_4-Pad19)") (class "Default")
      (node (ref "U5") (pin "19") (pinfunction "P2_4_19") (pintype "bidirectional+no_connect"))
    )
    (net (code "67") (name "unconnected-(U5-P2_7{slash}TX_IND-Pad11)") (class "Default")
      (node (ref "U5") (pin "11") (pinfunction "P2_7/TX_IND_11") (pintype "bidirectional+no_connect"))
    )
    (net (code "68") (name "unconnected-(U5-P3_1-Pad24)") (class "Default")
      (node (ref "U5") (pin "24") (pinfunction "P3_1_24") (pintype "bidirectional+no_connect"))
    )
    (net (code "69") (name "unconnected-(U5-P3_2-Pad25)") (class "Default")
      (node (ref "U5") (pin "25") (pinfunction "P3_2_25") (pintype "bidirectional+no_connect"))
    )
    (net (code "70") (name "unconnected-(U5-P3_4-Pad27)") (class "Default")
      (node (ref "U5") (pin "27") (pinfunction "P3_4_27") (pintype "bidirectional+no_connect"))
    )
    (net (code "71") (name "unconnected-(U5-P3_5-Pad28)") (class "Default")
      (node (ref "U5") (pin "28") (pinfunction "P3_5_28") (pintype "bidirectional+no_connect"))
    )
    (net (code "72") (name "unconnected-(U5-P3_6{slash}RTS-Pad17)") (class "Default")
      (node (ref "U5") (pin "17") (pinfunction "P3_6/RTS_17") (pintype "bidirectional+no_connect"))
    )
    (net (code "73") (name "unconnected-(U5-ULPC_O-Pad8)") (class "Default")
      (node (ref "U5") (pin "8") (pinfunction "ULPC_O_8") (pintype "power_in+no_connect"))
    )
    (net (code "74") (name "unconnected-(U5-VDD_IO-Pad6)") (class "Default")
      (node (ref "U5") (pin "6") (pinfunction "VDD_IO_6") (pintype "power_in+no_connect"))
    )
    (net (code "75") (name "unconnected-(U5-VDD_IO-Pad7)") (class "Default")
      (node (ref "U5") (pin "7") (pinfunction "VDD_IO_7") (pintype "power_in+no_connect"))
    )
  )
)
